# ideal_diode.net
KiCad netlist of a schematic drawn in Altium Designer
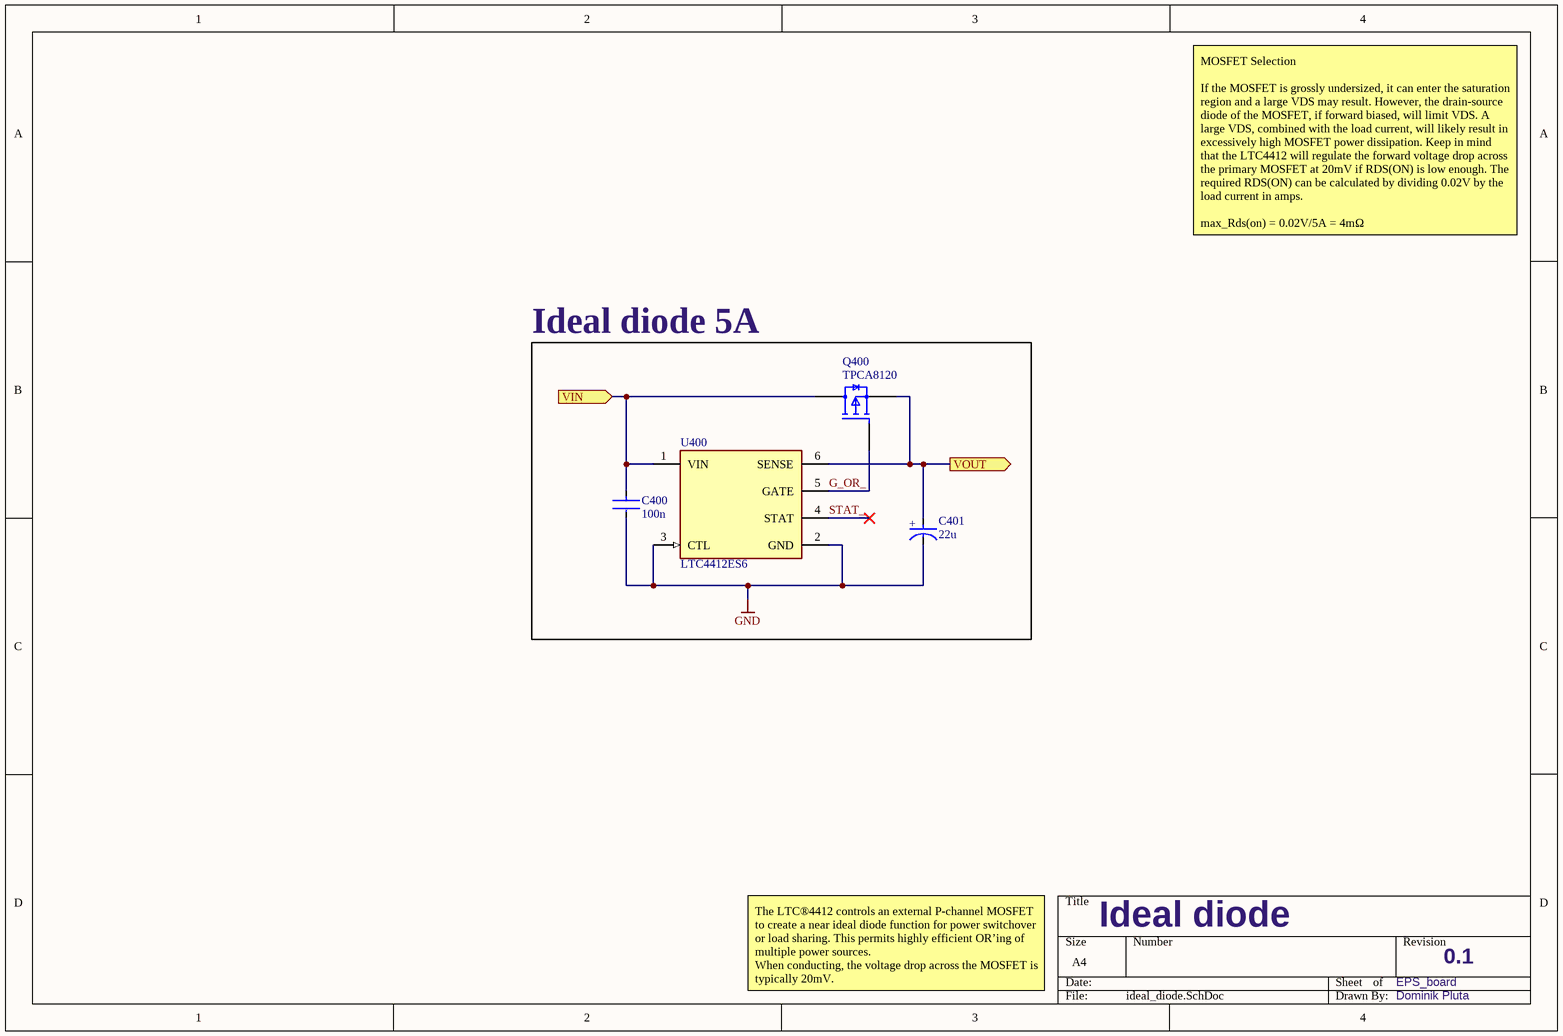
[diagram p0: ideal_diode.SchDoc]

(export (version "E")
  (design (tool "Eeschema 10.0.6"))
  (components
    (comp (ref "C400")
      (value "100n")
      (footprint "FP-C0603C-CF-MFG")
      (description "CAP 0.1 μF, X5R or X7R ceramic")
      (fields (field (name "TOLERANCE") "10"))
      (libsource (lib "Altium Content Vault") (part "b4654b650e69147ec39a6b967a45e02"))
    )
    (comp (ref "C401")
      (value "22u")
      (footprint "FP-T491B107K006AT-MFG")
      (description "CAP TANT 22UF 10% 6.3V 1411")
      (fields (field (name "TOLERANCE") "10%"))
      (libsource (lib "Altium Content Vault") (part "a00bbbee19879c290e62620ae7e47b1"))
    )
    (comp (ref "Q400")
      (value "TPCA8120")
      (footprint "TPCA8120")
      (description "MOSFET P-CH 30V 45A SOP Advance")
      (libsource (lib "TPCA8120") (part "TPCA8120"))
    )
    (comp (ref "U400")
      (value "LTC4412ES6")
      (footprint "FP-S6-6-05-08-1636-IPC_C")
      (description "IC OR CTRLR SRC SELECT TSOT23-6")
      (libsource (lib "Altium Content Vault") (part "07cb0f4431a3a7488227ca1baae77bb"))
    )
  )
  (nets
    (net (code "1") (name "/G_OR_") (class "Default")
      (node (ref "Q400") (pin "2") (pinfunction "G_2") (pintype "passive"))
      (node (ref "U400") (pin "5") (pinfunction "GATE_5") (pintype "passive"))
    )
    (net (code "2") (name "/STAT_") (class "Default")
      (node (ref "U400") (pin "4") (pinfunction "STAT_4") (pintype "open_collector+no_connect"))
    )
    (net (code "3") (name "/VIN") (class "Default")
      (node (ref "C400") (pin "1") (pinfunction "1_1") (pintype "passive"))
      (node (ref "Q400") (pin "3") (pinfunction "D_3") (pintype "passive"))
      (node (ref "U400") (pin "1") (pinfunction "VIN_1") (pintype "power_in"))
    )
    (net (code "4") (name "/VOUT") (class "Default")
      (node (ref "C401") (pin "2") (pinfunction "A_2") (pintype "passive"))
      (node (ref "Q400") (pin "1") (pinfunction "S_1") (pintype "passive"))
      (node (ref "U400") (pin "6") (pinfunction "SENSE_6") (pintype "passive"))
    )
    (net (code "5") (name "GND") (class "Default")
      (node (ref "C400") (pin "2") (pinfunction "2_2") (pintype "passive"))
      (node (ref "C401") (pin "1") (pinfunction "C_1") (pintype "passive"))
      (node (ref "U400") (pin "2") (pinfunction "GND_2") (pintype "power_in"))
      (node (ref "U400") (pin "3") (pinfunction "CTL_3") (pintype "input"))
    )
  )
)
